# AMC-SATA.net
KiCad netlist of a schematic drawn in Altium Designer
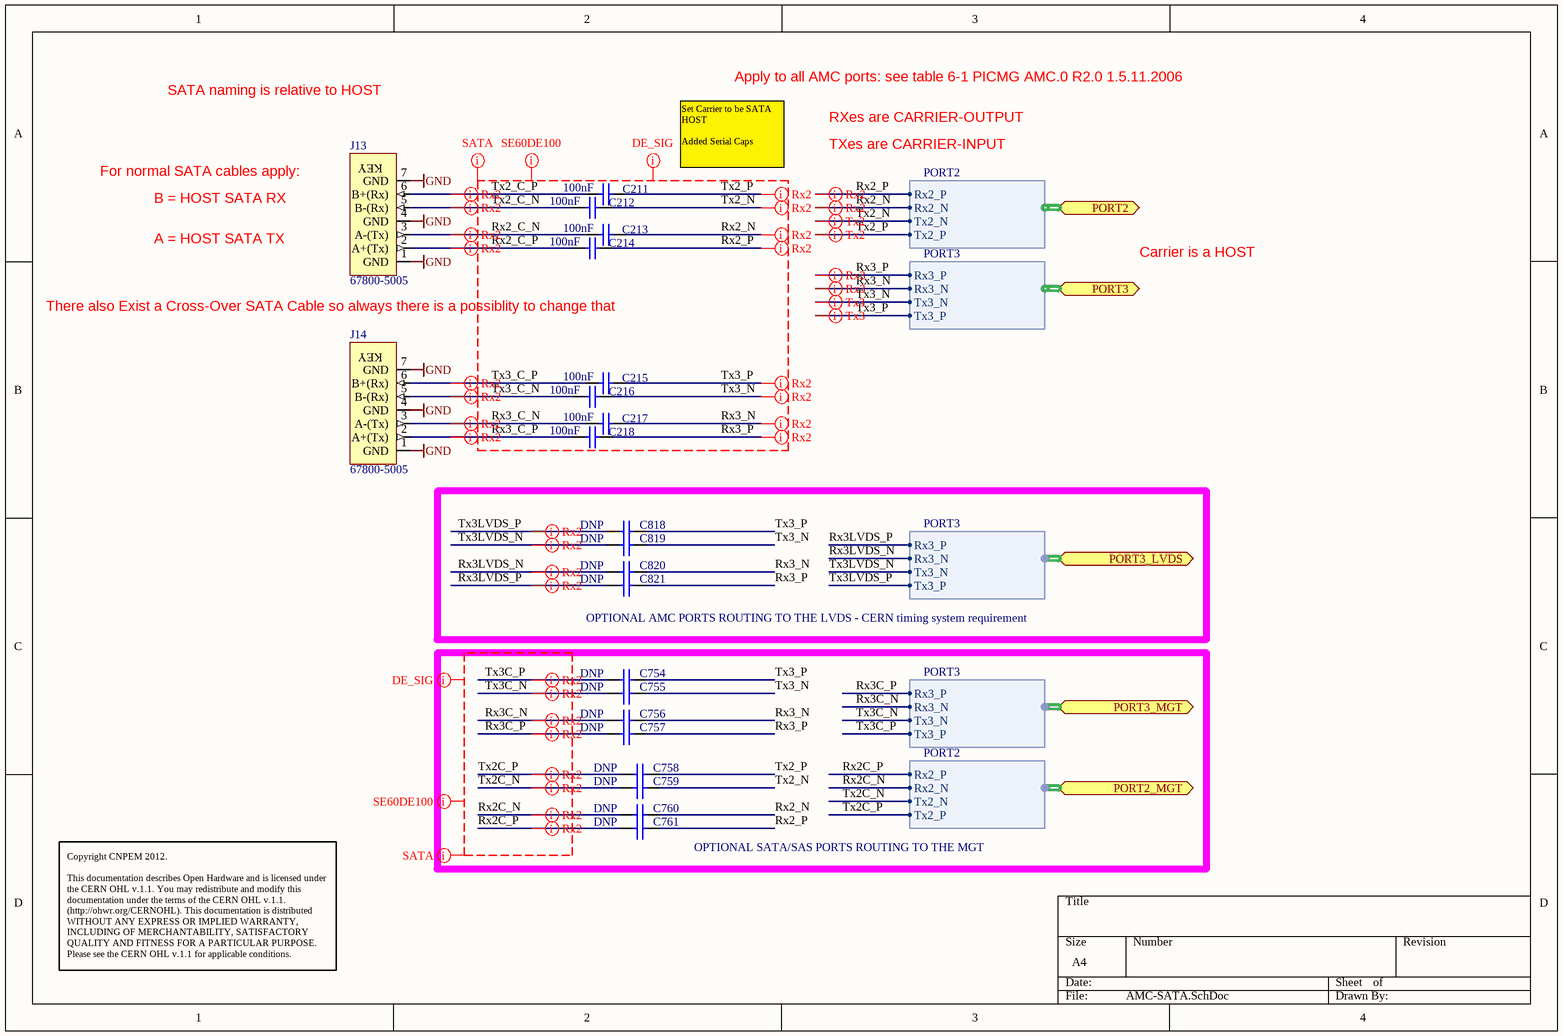
[diagram p0: AMC-SATA.SchDoc]

(export (version "E")
  (design (tool "Eeschema 10.0.6"))
  (components
    (comp (ref "C211")
      (value "100nF")
      (footprint "CAPC0603X33N")
      (description "Non-polarised capacitor")
      (fields
        (field (name "PART NUMBER") "CC0201_100NF_6.3V_10%_X5R")
        (field (name "VOLTAGE") "6.3V")
        (field (name "AUTHOR") "CERN DEM JLC")
      )
      (libsource (lib "Capacitors") (part "Capacitor - non polarized"))
    )
    (comp (ref "C212")
      (value "100nF")
      (footprint "CAPC0603X33N")
      (description "Non-polarised capacitor")
      (fields
        (field (name "PART NUMBER") "CC0201_100NF_6.3V_10%_X5R")
        (field (name "VOLTAGE") "6.3V")
        (field (name "AUTHOR") "CERN DEM JLC")
      )
      (libsource (lib "Capacitors") (part "Capacitor - non polarized"))
    )
    (comp (ref "C213")
      (value "100nF")
      (footprint "CAPC0603X33N")
      (description "Non-polarised capacitor")
      (fields
        (field (name "PART NUMBER") "CC0201_100NF_6.3V_10%_X5R")
        (field (name "VOLTAGE") "6.3V")
        (field (name "AUTHOR") "CERN DEM JLC")
      )
      (libsource (lib "Capacitors") (part "Capacitor - non polarized"))
    )
    (comp (ref "C214")
      (value "100nF")
      (footprint "CAPC0603X33N")
      (description "Non-polarised capacitor")
      (fields
        (field (name "PART NUMBER") "CC0201_100NF_6.3V_10%_X5R")
        (field (name "VOLTAGE") "6.3V")
        (field (name "AUTHOR") "CERN DEM JLC")
      )
      (libsource (lib "Capacitors") (part "Capacitor - non polarized"))
    )
    (comp (ref "C215")
      (value "100nF")
      (footprint "CAPC0603X33N")
      (description "Non-polarised capacitor")
      (fields
        (field (name "PART NUMBER") "CC0201_100NF_6.3V_10%_X5R")
        (field (name "VOLTAGE") "6.3V")
        (field (name "AUTHOR") "CERN DEM JLC")
      )
      (libsource (lib "Capacitors") (part "Capacitor - non polarized"))
    )
    (comp (ref "C216")
      (value "100nF")
      (footprint "CAPC0603X33N")
      (description "Non-polarised capacitor")
      (fields
        (field (name "PART NUMBER") "CC0201_100NF_6.3V_10%_X5R")
        (field (name "VOLTAGE") "6.3V")
        (field (name "AUTHOR") "CERN DEM JLC")
      )
      (libsource (lib "Capacitors") (part "Capacitor - non polarized"))
    )
    (comp (ref "C217")
      (value "100nF")
      (footprint "CAPC0603X33N")
      (description "Non-polarised capacitor")
      (fields
        (field (name "PART NUMBER") "CC0201_100NF_6.3V_10%_X5R")
        (field (name "VOLTAGE") "6.3V")
        (field (name "AUTHOR") "CERN DEM JLC")
      )
      (libsource (lib "Capacitors") (part "Capacitor - non polarized"))
    )
    (comp (ref "C218")
      (value "100nF")
      (footprint "CAPC0603X33N")
      (description "Non-polarised capacitor")
      (fields
        (field (name "PART NUMBER") "CC0201_100NF_6.3V_10%_X5R")
        (field (name "VOLTAGE") "6.3V")
        (field (name "AUTHOR") "CERN DEM JLC")
      )
      (libsource (lib "Capacitors") (part "Capacitor - non polarized"))
    )
    (comp (ref "C754")
      (value "DNP")
      (footprint "CAPC0603X33N")
      (description "Non-polarised capacitor")
      (fields
        (field (name "PART NUMBER") "CC0201_100NF_6.3V_10%_X5R")
        (field (name "VOLTAGE") "6.3V")
        (field (name "AUTHOR") "CERN DEM JLC")
      )
      (libsource (lib "Capacitors") (part "Capacitor - non polarized"))
    )
    (comp (ref "C755")
      (value "DNP")
      (footprint "CAPC0603X33N")
      (description "Non-polarised capacitor")
      (fields
        (field (name "PART NUMBER") "CC0201_100NF_6.3V_10%_X5R")
        (field (name "VOLTAGE") "6.3V")
        (field (name "AUTHOR") "CERN DEM JLC")
      )
      (libsource (lib "Capacitors") (part "Capacitor - non polarized"))
    )
    (comp (ref "C756")
      (value "DNP")
      (footprint "CAPC0603X33N")
      (description "Non-polarised capacitor")
      (fields
        (field (name "PART NUMBER") "CC0201_100NF_6.3V_10%_X5R")
        (field (name "VOLTAGE") "6.3V")
        (field (name "AUTHOR") "CERN DEM JLC")
      )
      (libsource (lib "Capacitors") (part "Capacitor - non polarized"))
    )
    (comp (ref "C757")
      (value "DNP")
      (footprint "CAPC0603X33N")
      (description "Non-polarised capacitor")
      (fields
        (field (name "PART NUMBER") "CC0201_100NF_6.3V_10%_X5R")
        (field (name "VOLTAGE") "6.3V")
        (field (name "AUTHOR") "CERN DEM JLC")
      )
      (libsource (lib "Capacitors") (part "Capacitor - non polarized"))
    )
    (comp (ref "C758")
      (value "DNP")
      (footprint "CAPC0603X33N")
      (description "Non-polarised capacitor")
      (fields
        (field (name "PART NUMBER") "CC0201_100NF_6.3V_10%_X5R")
        (field (name "VOLTAGE") "6.3V")
        (field (name "AUTHOR") "CERN DEM JLC")
      )
      (libsource (lib "Capacitors") (part "Capacitor - non polarized"))
    )
    (comp (ref "C759")
      (value "DNP")
      (footprint "CAPC0603X33N")
      (description "Non-polarised capacitor")
      (fields
        (field (name "PART NUMBER") "CC0201_100NF_6.3V_10%_X5R")
        (field (name "VOLTAGE") "6.3V")
        (field (name "AUTHOR") "CERN DEM JLC")
      )
      (libsource (lib "Capacitors") (part "Capacitor - non polarized"))
    )
    (comp (ref "C760")
      (value "DNP")
      (footprint "CAPC0603X33N")
      (description "Non-polarised capacitor")
      (fields
        (field (name "PART NUMBER") "CC0201_100NF_6.3V_10%_X5R")
        (field (name "VOLTAGE") "6.3V")
        (field (name "AUTHOR") "CERN DEM JLC")
      )
      (libsource (lib "Capacitors") (part "Capacitor - non polarized"))
    )
    (comp (ref "C761")
      (value "DNP")
      (footprint "CAPC0603X33N")
      (description "Non-polarised capacitor")
      (fields
        (field (name "PART NUMBER") "CC0201_100NF_6.3V_10%_X5R")
        (field (name "VOLTAGE") "6.3V")
        (field (name "AUTHOR") "CERN DEM JLC")
      )
      (libsource (lib "Capacitors") (part "Capacitor - non polarized"))
    )
    (comp (ref "C818")
      (value "DNP")
      (footprint "CAPC0603X33N")
      (description "Non-polarised capacitor")
      (fields
        (field (name "PART NUMBER") "CC0201_100NF_6.3V_10%_X5R")
        (field (name "VOLTAGE") "6.3V")
        (field (name "AUTHOR") "CERN DEM JLC")
      )
      (libsource (lib "Capacitors") (part "Capacitor - non polarized"))
    )
    (comp (ref "C819")
      (value "DNP")
      (footprint "CAPC0603X33N")
      (description "Non-polarised capacitor")
      (fields
        (field (name "PART NUMBER") "CC0201_100NF_6.3V_10%_X5R")
        (field (name "VOLTAGE") "6.3V")
        (field (name "AUTHOR") "CERN DEM JLC")
      )
      (libsource (lib "Capacitors") (part "Capacitor - non polarized"))
    )
    (comp (ref "C820")
      (value "DNP")
      (footprint "CAPC0603X33N")
      (description "Non-polarised capacitor")
      (fields
        (field (name "PART NUMBER") "CC0201_100NF_6.3V_10%_X5R")
        (field (name "VOLTAGE") "6.3V")
        (field (name "AUTHOR") "CERN DEM JLC")
      )
      (libsource (lib "Capacitors") (part "Capacitor - non polarized"))
    )
    (comp (ref "C821")
      (value "DNP")
      (footprint "CAPC0603X33N")
      (description "Non-polarised capacitor")
      (fields
        (field (name "PART NUMBER") "CC0201_100NF_6.3V_10%_X5R")
        (field (name "VOLTAGE") "6.3V")
        (field (name "AUTHOR") "CERN DEM JLC")
      )
      (libsource (lib "Capacitors") (part "Capacitor - non polarized"))
    )
    (comp (ref "J13")
      (value "67800-5005")
      (footprint "CON_SATA_V")
      (description "SATA conenctor  PCB Molex")
      (libsource (lib "AMC_FMC_Carrier") (part "CON_SATA_V"))
    )
    (comp (ref "J14")
      (value "67800-5005")
      (footprint "CON_SATA_V")
      (description "SATA conenctor  PCB Molex")
      (libsource (lib "AMC_FMC_Carrier") (part "CON_SATA_V"))
    )
  )
  (nets
    (net (code "3") (name "/Rx2C_N") (class "Default")
      (node (ref "C760") (pin "1") (pinfunction "1_1") (pintype "passive"))
    )
    (net (code "4") (name "/Rx2C_P") (class "Default")
      (node (ref "C761") (pin "1") (pinfunction "1_1") (pintype "passive"))
    )
    (net (code "5") (name "/Rx2_C_N") (class "Default")
      (node (ref "C213") (pin "1") (pinfunction "1_1") (pintype "passive"))
      (node (ref "J13") (pin "3") (pinfunction "A-(Tx)_3") (pintype "output"))
    )
    (net (code "6") (name "/Rx2_C_P") (class "Default")
      (node (ref "C214") (pin "1") (pinfunction "1_1") (pintype "passive"))
      (node (ref "J13") (pin "2") (pinfunction "A+(Tx)_2") (pintype "output"))
    )
    (net (code "7") (name "/Rx2_N") (class "Default")
      (node (ref "C213") (pin "2") (pinfunction "2_2") (pintype "passive"))
      (node (ref "C760") (pin "2") (pinfunction "2_2") (pintype "passive"))
    )
    (net (code "8") (name "/Rx2_P") (class "Default")
      (node (ref "C214") (pin "2") (pinfunction "2_2") (pintype "passive"))
      (node (ref "C761") (pin "2") (pinfunction "2_2") (pintype "passive"))
    )
    (net (code "9") (name "/Rx3C_N") (class "Default")
      (node (ref "C756") (pin "1") (pinfunction "1_1") (pintype "passive"))
    )
    (net (code "10") (name "/Rx3C_P") (class "Default")
      (node (ref "C757") (pin "1") (pinfunction "1_1") (pintype "passive"))
    )
    (net (code "11") (name "/Rx3LVDS_N") (class "Default")
      (node (ref "C820") (pin "1") (pinfunction "1_1") (pintype "passive"))
    )
    (net (code "12") (name "/Rx3LVDS_P") (class "Default")
      (node (ref "C821") (pin "1") (pinfunction "1_1") (pintype "passive"))
    )
    (net (code "13") (name "/Rx3_C_N") (class "Default")
      (node (ref "C217") (pin "1") (pinfunction "1_1") (pintype "passive"))
      (node (ref "J14") (pin "3") (pinfunction "A-(Tx)_3") (pintype "output"))
    )
    (net (code "14") (name "/Rx3_C_P") (class "Default")
      (node (ref "C218") (pin "1") (pinfunction "1_1") (pintype "passive"))
      (node (ref "J14") (pin "2") (pinfunction "A+(Tx)_2") (pintype "output"))
    )
    (net (code "15") (name "/Rx3_N") (class "Default")
      (node (ref "C217") (pin "2") (pinfunction "2_2") (pintype "passive"))
      (node (ref "C756") (pin "2") (pinfunction "2_2") (pintype "passive"))
      (node (ref "C820") (pin "2") (pinfunction "2_2") (pintype "passive"))
    )
    (net (code "16") (name "/Rx3_P") (class "Default")
      (node (ref "C218") (pin "2") (pinfunction "2_2") (pintype "passive"))
      (node (ref "C757") (pin "2") (pinfunction "2_2") (pintype "passive"))
      (node (ref "C821") (pin "2") (pinfunction "2_2") (pintype "passive"))
    )
    (net (code "17") (name "/Tx2C_N") (class "Default")
      (node (ref "C759") (pin "1") (pinfunction "1_1") (pintype "passive"))
    )
    (net (code "18") (name "/Tx2C_P") (class "Default")
      (node (ref "C758") (pin "1") (pinfunction "1_1") (pintype "passive"))
    )
    (net (code "19") (name "/Tx2_C_N") (class "Default")
      (node (ref "C212") (pin "1") (pinfunction "1_1") (pintype "passive"))
      (node (ref "J13") (pin "5") (pinfunction "B-(Rx)_5") (pintype "input"))
    )
    (net (code "20") (name "/Tx2_C_P") (class "Default")
      (node (ref "C211") (pin "1") (pinfunction "1_1") (pintype "passive"))
      (node (ref "J13") (pin "6") (pinfunction "B+(Rx)_6") (pintype "input"))
    )
    (net (code "21") (name "/Tx2_N") (class "Default")
      (node (ref "C212") (pin "2") (pinfunction "2_2") (pintype "passive"))
      (node (ref "C759") (pin "2") (pinfunction "2_2") (pintype "passive"))
    )
    (net (code "22") (name "/Tx2_P") (class "Default")
      (node (ref "C211") (pin "2") (pinfunction "2_2") (pintype "passive"))
      (node (ref "C758") (pin "2") (pinfunction "2_2") (pintype "passive"))
    )
    (net (code "23") (name "/Tx3C_N") (class "Default")
      (node (ref "C755") (pin "1") (pinfunction "1_1") (pintype "passive"))
    )
    (net (code "24") (name "/Tx3C_P") (class "Default")
      (node (ref "C754") (pin "1") (pinfunction "1_1") (pintype "passive"))
    )
    (net (code "25") (name "/Tx3LVDS_N") (class "Default")
      (node (ref "C819") (pin "1") (pinfunction "1_1") (pintype "passive"))
    )
    (net (code "26") (name "/Tx3LVDS_P") (class "Default")
      (node (ref "C818") (pin "1") (pinfunction "1_1") (pintype "passive"))
    )
    (net (code "27") (name "/Tx3_C_N") (class "Default")
      (node (ref "C216") (pin "1") (pinfunction "1_1") (pintype "passive"))
      (node (ref "J14") (pin "5") (pinfunction "B-(Rx)_5") (pintype "input"))
    )
    (net (code "28") (name "/Tx3_C_P") (class "Default")
      (node (ref "C215") (pin "1") (pinfunction "1_1") (pintype "passive"))
      (node (ref "J14") (pin "6") (pinfunction "B+(Rx)_6") (pintype "input"))
    )
    (net (code "29") (name "/Tx3_N") (class "Default")
      (node (ref "C216") (pin "2") (pinfunction "2_2") (pintype "passive"))
      (node (ref "C755") (pin "2") (pinfunction "2_2") (pintype "passive"))
      (node (ref "C819") (pin "2") (pinfunction "2_2") (pintype "passive"))
    )
    (net (code "30") (name "/Tx3_P") (class "Default")
      (node (ref "C215") (pin "2") (pinfunction "2_2") (pintype "passive"))
      (node (ref "C754") (pin "2") (pinfunction "2_2") (pintype "passive"))
      (node (ref "C818") (pin "2") (pinfunction "2_2") (pintype "passive"))
    )
    (net (code "33") (name "GND") (class "Default")
      (node (ref "J13") (pin "1") (pinfunction "GND_1") (pintype "power_in"))
      (node (ref "J13") (pin "4") (pinfunction "GND_4") (pintype "power_in"))
      (node (ref "J13") (pin "7") (pinfunction "GND_7") (pintype "power_in"))
      (node (ref "J14") (pin "1") (pinfunction "GND_1") (pintype "power_in"))
      (node (ref "J14") (pin "4") (pinfunction "GND_4") (pintype "power_in"))
      (node (ref "J14") (pin "7") (pinfunction "GND_7") (pintype "power_in"))
    )
  )
)
